# schema.net
KiCad netlist of a schematic drawn in EAGLE
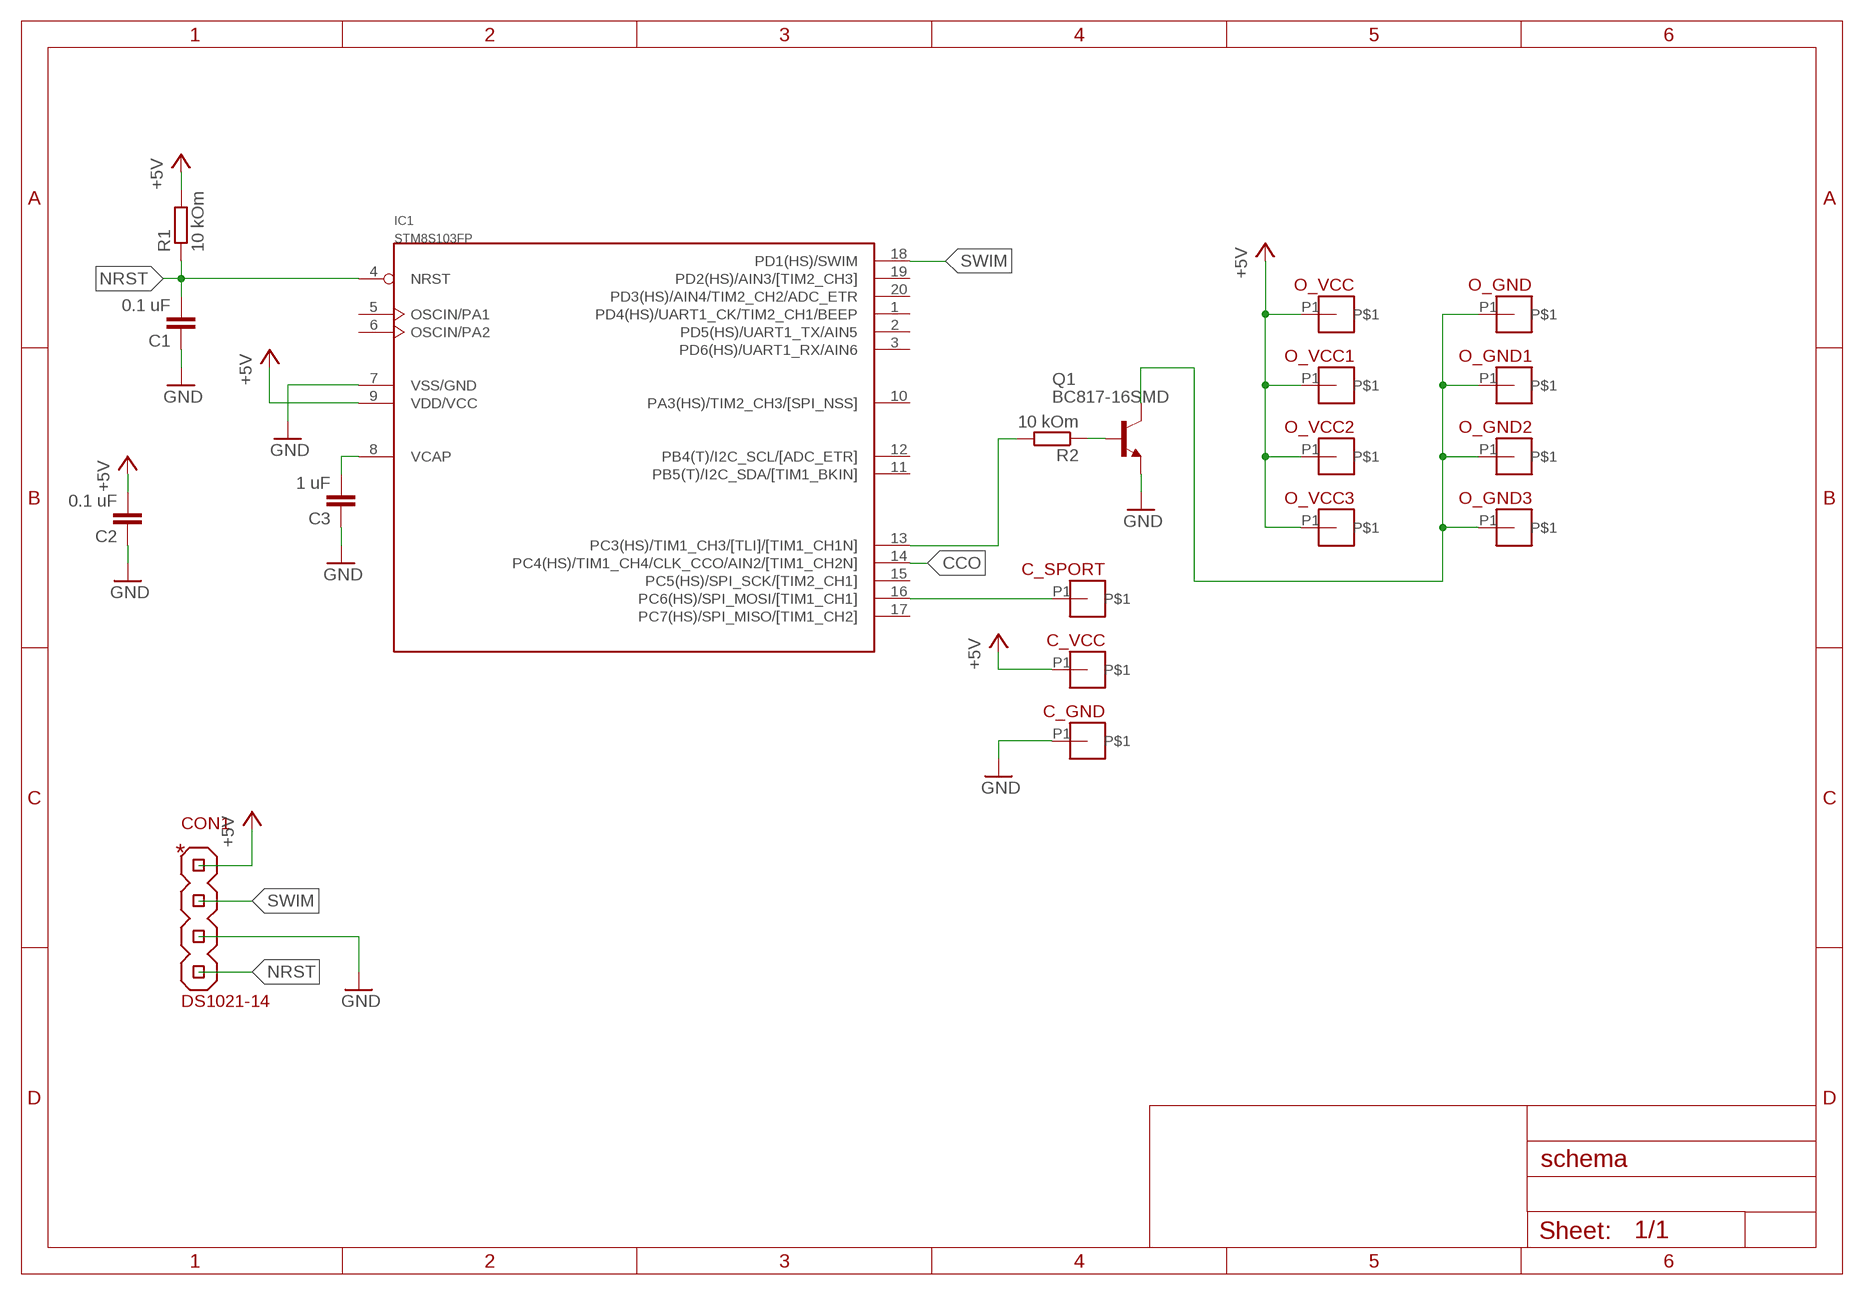
[diagram p0: schematic, sheet 1]

(export (version "E")
  (design (tool "Eeschema 10.0.6"))
  (components
    (comp (ref "C1")
      (value "0.1 uF")
      (footprint "eagle-import:C0603")
      (libsource (lib "eagle-import") (part "C-EUC0603"))
    )
    (comp (ref "C2")
      (value "0.1 uF")
      (footprint "eagle-import:C0603")
      (libsource (lib "eagle-import") (part "C-EUC0603"))
    )
    (comp (ref "C3")
      (value "1 uF")
      (footprint "eagle-import:C0603")
      (libsource (lib "eagle-import") (part "C-EUC0603"))
    )
    (comp (ref "CON1")
      (value "DS1021-14")
      (footprint "eagle-import:DS1021-1_4")
      (libsource (lib "eagle-import") (part "DS1021-14"))
    )
    (comp (ref "C_GND")
      (value "PAD1_0.8")
      (footprint "eagle-import:PAD1_0.8")
      (libsource (lib "eagle-import") (part "PAD1_0.8"))
    )
    (comp (ref "C_SPORT")
      (value "PAD1_0.8")
      (footprint "eagle-import:PAD1_0.8")
      (libsource (lib "eagle-import") (part "PAD1_0.8"))
    )
    (comp (ref "C_VCC")
      (value "PAD1_0.8")
      (footprint "eagle-import:PAD1_0.8")
      (libsource (lib "eagle-import") (part "PAD1_0.8"))
    )
    (comp (ref "IC1")
      (value "STM8S103FP")
      (footprint "eagle-import:TSSOP20")
      (libsource (lib "eagle-import") (part "STM8S103FP"))
    )
    (comp (ref "O_GND")
      (value "PAD1_0.8")
      (footprint "eagle-import:PAD1_0.8")
      (libsource (lib "eagle-import") (part "PAD1_0.8"))
    )
    (comp (ref "O_GND1")
      (value "PAD1_0.8")
      (footprint "eagle-import:PAD1_0.8")
      (libsource (lib "eagle-import") (part "PAD1_0.8"))
    )
    (comp (ref "O_GND2")
      (value "PAD1_0.8")
      (footprint "eagle-import:PAD1_0.8")
      (libsource (lib "eagle-import") (part "PAD1_0.8"))
    )
    (comp (ref "O_GND3")
      (value "PAD1_0.8")
      (footprint "eagle-import:PAD1_0.8")
      (libsource (lib "eagle-import") (part "PAD1_0.8"))
    )
    (comp (ref "O_VCC")
      (value "PAD1_0.8")
      (footprint "eagle-import:PAD1_0.8")
      (libsource (lib "eagle-import") (part "PAD1_0.8"))
    )
    (comp (ref "O_VCC1")
      (value "PAD1_0.8")
      (footprint "eagle-import:PAD1_0.8")
      (libsource (lib "eagle-import") (part "PAD1_0.8"))
    )
    (comp (ref "O_VCC2")
      (value "PAD1_0.8")
      (footprint "eagle-import:PAD1_0.8")
      (libsource (lib "eagle-import") (part "PAD1_0.8"))
    )
    (comp (ref "O_VCC3")
      (value "PAD1_0.8")
      (footprint "eagle-import:PAD1_0.8")
      (libsource (lib "eagle-import") (part "PAD1_0.8"))
    )
    (comp (ref "Q1")
      (value "BC817-16SMD")
      (footprint "eagle-import:SOT23-BEC")
      (libsource (lib "eagle-import") (part "BC817SMD-16"))
    )
    (comp (ref "R1")
      (value "10 kOm")
      (footprint "eagle-import:R0603")
      (libsource (lib "eagle-import") (part "R-EU_R0603"))
    )
    (comp (ref "R2")
      (value "10 kOm")
      (footprint "eagle-import:R0603")
      (libsource (lib "eagle-import") (part "R-EU_R0603"))
    )
  )
  (nets
    (net (code "1") (name "+5V") (class "Default")
      (node (ref "C2") (pin "2") (pinfunction "2_2") (pintype "passive"))
      (node (ref "CON1") (pin "P1") (pinfunction "P1_P1") (pintype "bidirectional"))
      (node (ref "C_VCC") (pin "P1") (pinfunction "P$1_P1") (pintype "bidirectional"))
      (node (ref "IC1") (pin "9") (pinfunction "VDD/VCC_9") (pintype "power_in"))
      (node (ref "O_VCC") (pin "P1") (pinfunction "P$1_P1") (pintype "bidirectional"))
      (node (ref "O_VCC1") (pin "P1") (pinfunction "P$1_P1") (pintype "bidirectional"))
      (node (ref "O_VCC2") (pin "P1") (pinfunction "P$1_P1") (pintype "bidirectional"))
      (node (ref "O_VCC3") (pin "P1") (pinfunction "P$1_P1") (pintype "bidirectional"))
      (node (ref "R1") (pin "2") (pinfunction "2_2") (pintype "passive"))
    )
    (net (code "2") (name "CCO") (class "Default")
      (node (ref "IC1") (pin "14") (pinfunction "PC4(HS)/TIM1_CH4/CLK_CCO/AIN2/[TIM1_CH2N]_14") (pintype "bidirectional"))
    )
    (net (code "3") (name "GND") (class "Default")
      (node (ref "C1") (pin "1") (pinfunction "1_1") (pintype "passive"))
      (node (ref "C2") (pin "1") (pinfunction "1_1") (pintype "passive"))
      (node (ref "C3") (pin "1") (pinfunction "1_1") (pintype "passive"))
      (node (ref "CON1") (pin "P3") (pinfunction "P3_P3") (pintype "bidirectional"))
      (node (ref "C_GND") (pin "P1") (pinfunction "P$1_P1") (pintype "bidirectional"))
      (node (ref "IC1") (pin "7") (pinfunction "VSS/GND_7") (pintype "power_in"))
      (node (ref "Q1") (pin "E") (pinfunction "E_E") (pintype "passive"))
    )
    (net (code "4") (name "NRST") (class "Default")
      (node (ref "C1") (pin "2") (pinfunction "2_2") (pintype "passive"))
      (node (ref "CON1") (pin "P4") (pinfunction "P4_P4") (pintype "bidirectional"))
      (node (ref "IC1") (pin "4") (pinfunction "NRST_4") (pintype "bidirectional"))
      (node (ref "R1") (pin "1") (pinfunction "1_1") (pintype "passive"))
    )
    (net (code "5") (name "Net-(C_SPORT-P$1)") (class "Default")
      (node (ref "C_SPORT") (pin "P1") (pinfunction "P$1_P1") (pintype "bidirectional"))
      (node (ref "IC1") (pin "16") (pinfunction "PC6(HS)/SPI_MOSI/[TIM1_CH1]_16") (pintype "bidirectional"))
    )
    (net (code "6") (name "Net-(IC1-PC3(HS){slash}TIM1_CH3{slash}[TLI]{slash}[TIM1_CH1N])") (class "Default")
      (node (ref "IC1") (pin "13") (pinfunction "PC3(HS)/TIM1_CH3/[TLI]/[TIM1_CH1N]_13") (pintype "bidirectional"))
      (node (ref "R2") (pin "2") (pinfunction "2_2") (pintype "passive"))
    )
    (net (code "7") (name "Net-(IC1-VCAP)") (class "Default")
      (node (ref "C3") (pin "2") (pinfunction "2_2") (pintype "passive"))
      (node (ref "IC1") (pin "8") (pinfunction "VCAP_8") (pintype "power_in"))
    )
    (net (code "8") (name "Net-(O_GND-P$1)") (class "Default")
      (node (ref "O_GND") (pin "P1") (pinfunction "P$1_P1") (pintype "bidirectional"))
      (node (ref "O_GND1") (pin "P1") (pinfunction "P$1_P1") (pintype "bidirectional"))
      (node (ref "O_GND2") (pin "P1") (pinfunction "P$1_P1") (pintype "bidirectional"))
      (node (ref "O_GND3") (pin "P1") (pinfunction "P$1_P1") (pintype "bidirectional"))
      (node (ref "Q1") (pin "C") (pinfunction "C_C") (pintype "passive"))
    )
    (net (code "9") (name "Net-(Q1-PadB)") (class "Default")
      (node (ref "Q1") (pin "B") (pinfunction "B_B") (pintype "passive"))
      (node (ref "R2") (pin "1") (pinfunction "1_1") (pintype "passive"))
    )
    (net (code "10") (name "SWIM") (class "Default")
      (node (ref "CON1") (pin "P2") (pinfunction "P2_P2") (pintype "bidirectional"))
      (node (ref "IC1") (pin "18") (pinfunction "PD1(HS)/SWIM_18") (pintype "bidirectional"))
    )
    (net (code "11") (name "unconnected-(IC1-OSCIN{slash}PA1-Pad5)") (class "Default")
      (node (ref "IC1") (pin "5") (pinfunction "OSCIN/PA1_5") (pintype "bidirectional"))
    )
    (net (code "12") (name "unconnected-(IC1-OSCIN{slash}PA2-Pad6)") (class "Default")
      (node (ref "IC1") (pin "6") (pinfunction "OSCIN/PA2_6") (pintype "bidirectional"))
    )
    (net (code "13") (name "unconnected-(IC1-PA3(HS){slash}TIM2_CH3{slash}[SPI_NSS]-Pad10)") (class "Default")
      (node (ref "IC1") (pin "10") (pinfunction "PA3(HS)/TIM2_CH3/[SPI_NSS]_10") (pintype "bidirectional"))
    )
    (net (code "14") (name "unconnected-(IC1-PB4(T){slash}I2C_SCL{slash}[ADC_ETR]-Pad12)") (class "Default")
      (node (ref "IC1") (pin "12") (pinfunction "PB4(T)/I2C_SCL/[ADC_ETR]_12") (pintype "bidirectional"))
    )
    (net (code "15") (name "unconnected-(IC1-PB5(T){slash}I2C_SDA{slash}[TIM1_BKIN]-Pad11)") (class "Default")
      (node (ref "IC1") (pin "11") (pinfunction "PB5(T)/I2C_SDA/[TIM1_BKIN]_11") (pintype "bidirectional"))
    )
    (net (code "16") (name "unconnected-(IC1-PC5(HS){slash}SPI_SCK{slash}[TIM2_CH1]-Pad15)") (class "Default")
      (node (ref "IC1") (pin "15") (pinfunction "PC5(HS)/SPI_SCK/[TIM2_CH1]_15") (pintype "bidirectional"))
    )
    (net (code "17") (name "unconnected-(IC1-PC7(HS){slash}SPI_MISO{slash}[TIM1_CH2]-Pad17)") (class "Default")
      (node (ref "IC1") (pin "17") (pinfunction "PC7(HS)/SPI_MISO/[TIM1_CH2]_17") (pintype "bidirectional"))
    )
    (net (code "18") (name "unconnected-(IC1-PD2(HS){slash}AIN3{slash}[TIM2_CH3]-Pad19)") (class "Default")
      (node (ref "IC1") (pin "19") (pinfunction "PD2(HS)/AIN3/[TIM2_CH3]_19") (pintype "bidirectional"))
    )
    (net (code "19") (name "unconnected-(IC1-PD3(HS){slash}AIN4{slash}TIM2_CH2{slash}ADC_ETR-Pad20)") (class "Default")
      (node (ref "IC1") (pin "20") (pinfunction "PD3(HS)/AIN4/TIM2_CH2/ADC_ETR_20") (pintype "bidirectional"))
    )
    (net (code "20") (name "unconnected-(IC1-PD4(HS){slash}UART1_CK{slash}TIM2_CH1{slash}BEEP-Pad1)") (class "Default")
      (node (ref "IC1") (pin "1") (pinfunction "PD4(HS)/UART1_CK/TIM2_CH1/BEEP_1") (pintype "bidirectional"))
    )
    (net (code "21") (name "unconnected-(IC1-PD5(HS){slash}UART1_TX{slash}AIN5-Pad2)") (class "Default")
      (node (ref "IC1") (pin "2") (pinfunction "PD5(HS)/UART1_TX/AIN5_2") (pintype "bidirectional"))
    )
    (net (code "22") (name "unconnected-(IC1-PD6(HS){slash}UART1_RX{slash}AIN6-Pad3)") (class "Default")
      (node (ref "IC1") (pin "3") (pinfunction "PD6(HS)/UART1_RX/AIN6_3") (pintype "bidirectional"))
    )
  )
)
